# Power_Sheet.net
KiCad netlist of a schematic drawn in Altium Designer
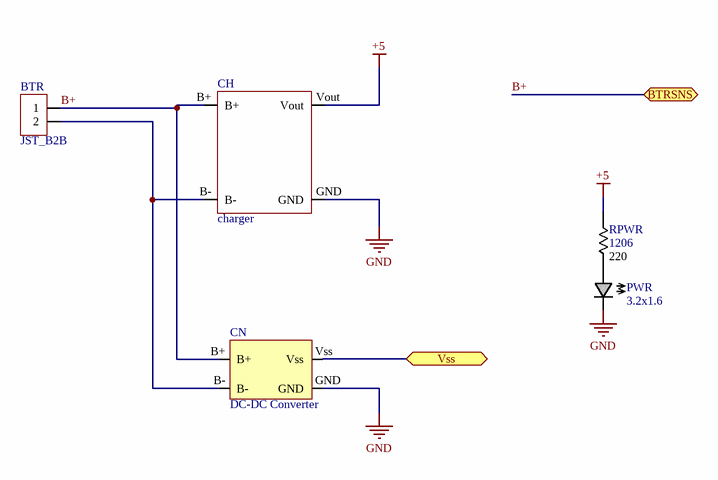
[diagram p0: Power_Sheet.SchDoc]

(export (version "E")
  (design (tool "Eeschema 10.0.6"))
  (components
    (comp (ref "BTR") (value "JST_B2B") (footprint "JST_B2B") (libsource (lib "JST_B2B") (part "JST_B2B")))
    (comp (ref "CH")
      (value "charger")
      (footprint "1S_Charger")
      (libsource (lib "1S_Charger") (part "charger"))
    )
    (comp (ref "CN")
      (value "DC-DC Converter")
      (footprint "DC-DC Conv")
      (libsource (lib "DC_DC_Converter") (part "DC-DC Converter"))
    )
    (comp (ref "PWR") (value "3.2x1.6") (footprint "LED3_2X1_6") (libsource (lib "LED_3d2_1d6") (part "led")))
    (comp (ref "RPWR")
      (value "1206")
      (footprint "1206")
      (fields (field (name "ALTIUM_VALUE") "220"))
      (libsource (lib "Res_3_2__1_6") (part "1206"))
    )
  )
  (nets
    (net (code "1") (name "+5") (class "Default")
      (node (ref "CH") (pin "Vout") (pinfunction "Vout_Vout") (pintype "passive"))
      (node (ref "RPWR") (pin "2") (pinfunction "2_2") (pintype "passive"))
    )
    (net (code "2") (name "/B+") (class "Default")
      (node (ref "BTR") (pin "1") (pinfunction "1_1") (pintype "passive"))
      (node (ref "CH") (pin "B+") (pinfunction "B+_B+") (pintype "passive"))
      (node (ref "CN") (pin "B+") (pinfunction "B+_B+") (pintype "passive"))
    )
    (net (code "3") (name "/Vss") (class "Default")
      (node (ref "CN") (pin "Vss") (pinfunction "Vss_Vss") (pintype "passive"))
    )
    (net (code "4") (name "GND") (class "Default")
      (node (ref "CH") (pin "GND") (pinfunction "GND_GND") (pintype "passive"))
      (node (ref "CN") (pin "GND") (pinfunction "GND_GND") (pintype "passive"))
      (node (ref "PWR") (pin "C") (pinfunction "C_C") (pintype "passive"))
    )
    (net (code "5") (name "Net-(BTR-Pad2)") (class "Default")
      (node (ref "BTR") (pin "2") (pinfunction "2_2") (pintype "passive"))
      (node (ref "CH") (pin "B-") (pinfunction "B-_B-") (pintype "passive"))
      (node (ref "CN") (pin "B-") (pinfunction "B-_B-") (pintype "passive"))
    )
    (net (code "6") (name "Net-(PWR-PadA)") (class "Default")
      (node (ref "PWR") (pin "A") (pinfunction "A_A") (pintype "passive"))
      (node (ref "RPWR") (pin "1") (pinfunction "1_1") (pintype "passive"))
    )
  )
)
